# PCFX_Contrl_Socket_rev_B.net
KiCad netlist of a schematic drawn in EAGLE
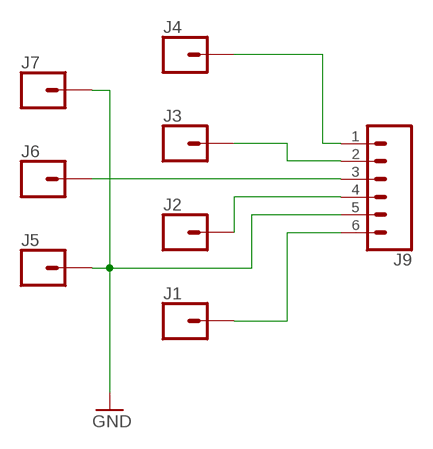
[diagram p0: schematic, sheet 1]

(export (version "E")
  (design (tool "Eeschema 10.0.6"))
  (components
    (comp (ref "J1")
      (value "CONN_01PTH_NO_SILK_YES_STOP")
      (footprint "eagle-import:1X01_NO_SILK")
      (libsource (lib "eagle-import") (part "CONN_01PTH_NO_SILK_YES_STOP"))
    )
    (comp (ref "J2")
      (value "CONN_01PTH_NO_SILK_YES_STOP")
      (footprint "eagle-import:1X01_NO_SILK")
      (libsource (lib "eagle-import") (part "CONN_01PTH_NO_SILK_YES_STOP"))
    )
    (comp (ref "J3")
      (value "CONN_01PTH_NO_SILK_YES_STOP")
      (footprint "eagle-import:1X01_NO_SILK")
      (libsource (lib "eagle-import") (part "CONN_01PTH_NO_SILK_YES_STOP"))
    )
    (comp (ref "J4")
      (value "CONN_01PTH_NO_SILK_YES_STOP")
      (footprint "eagle-import:1X01_NO_SILK")
      (libsource (lib "eagle-import") (part "CONN_01PTH_NO_SILK_YES_STOP"))
    )
    (comp (ref "J5")
      (value "CONN_01PTH_NO_SILK_YES_STOP")
      (footprint "eagle-import:1X01_NO_SILK")
      (libsource (lib "eagle-import") (part "CONN_01PTH_NO_SILK_YES_STOP"))
    )
    (comp (ref "J6")
      (value "CONN_01PTH_NO_SILK_YES_STOP")
      (footprint "eagle-import:1X01_NO_SILK")
      (libsource (lib "eagle-import") (part "CONN_01PTH_NO_SILK_YES_STOP"))
    )
    (comp (ref "J7")
      (value "CONN_01PTH_NO_SILK_YES_STOP")
      (footprint "eagle-import:1X01_NO_SILK")
      (libsource (lib "eagle-import") (part "CONN_01PTH_NO_SILK_YES_STOP"))
    )
    (comp (ref "J9")
      (value "CONN_06NO_SILK_FEMALE_PTH")
      (footprint "eagle-import:1X06_NO_SILK")
      (libsource (lib "eagle-import") (part "CONN_06NO_SILK_FEMALE_PTH"))
    )
  )
  (nets
    (net (code "1") (name "GND") (class "Default")
      (node (ref "J5") (pin "1") (pinfunction "1_1") (pintype "passive"))
      (node (ref "J7") (pin "1") (pinfunction "1_1") (pintype "passive"))
      (node (ref "J9") (pin "5") (pinfunction "5_5") (pintype "passive"))
    )
    (net (code "2") (name "Net-(J1-Pad1)") (class "Default")
      (node (ref "J1") (pin "1") (pinfunction "1_1") (pintype "passive"))
      (node (ref "J9") (pin "6") (pinfunction "6_6") (pintype "passive"))
    )
    (net (code "3") (name "Net-(J2-Pad1)") (class "Default")
      (node (ref "J2") (pin "1") (pinfunction "1_1") (pintype "passive"))
      (node (ref "J9") (pin "4") (pinfunction "4_4") (pintype "passive"))
    )
    (net (code "4") (name "Net-(J3-Pad1)") (class "Default")
      (node (ref "J3") (pin "1") (pinfunction "1_1") (pintype "passive"))
      (node (ref "J9") (pin "2") (pinfunction "2_2") (pintype "passive"))
    )
    (net (code "5") (name "Net-(J4-Pad1)") (class "Default")
      (node (ref "J4") (pin "1") (pinfunction "1_1") (pintype "passive"))
      (node (ref "J9") (pin "1") (pinfunction "1_1") (pintype "passive"))
    )
    (net (code "6") (name "Net-(J6-Pad1)") (class "Default")
      (node (ref "J6") (pin "1") (pinfunction "1_1") (pintype "passive"))
      (node (ref "J9") (pin "3") (pinfunction "3_3") (pintype "passive"))
    )
  )
)
